# Solar_Charge_Controller.net
KiCad netlist of a schematic drawn in EAGLE
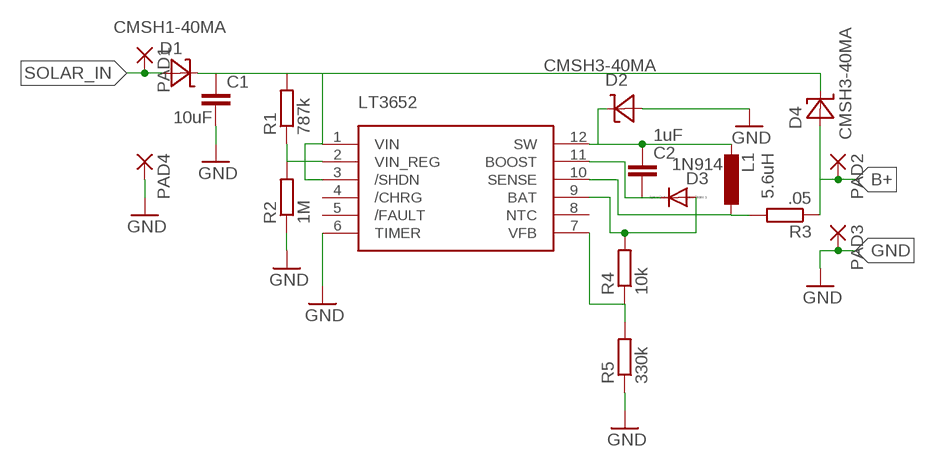
[diagram p0: schematic, sheet 1]

(export (version "E")
  (design (tool "Eeschema 10.0.6"))
  (components
    (comp (ref "C1")
      (value "10uF")
      (footprint "eagle-import:C0805")
      (libsource (lib "eagle-import") (part "C-EUC0805"))
    )
    (comp (ref "C2")
      (value "1uF")
      (footprint "eagle-import:C0603")
      (libsource (lib "eagle-import") (part "C-EUC0603"))
    )
    (comp (ref "D1")
      (value "CMSH1-40MA")
      (footprint "eagle-import:DO-214AC")
      (libsource (lib "eagle-import") (part "CMSH1-40MA"))
    )
    (comp (ref "D2")
      (value "CMSH3-40MA")
      (footprint "eagle-import:DO-214AC")
      (libsource (lib "eagle-import") (part "CMSH3-40MA"))
    )
    (comp (ref "D3")
      (value "1N914")
      (footprint "eagle-import:SOD523")
      (libsource (lib "eagle-import") (part "1N914"))
    )
    (comp (ref "D4")
      (value "CMSH3-40MA")
      (footprint "eagle-import:DO-214AC")
      (libsource (lib "eagle-import") (part "CMSH3-40MA"))
    )
    (comp (ref "L1")
      (value "5.6uH")
      (footprint "eagle-import:1008(2510METRIC)")
      (libsource (lib "eagle-import") (part "L-EU1008"))
    )
    (comp (ref "PAD1")
      (value "SMD5")
      (footprint "eagle-import:SMD2,54-5,08")
      (libsource (lib "eagle-import") (part "SMD5"))
    )
    (comp (ref "PAD2")
      (value "SMD5")
      (footprint "eagle-import:SMD2,54-5,08")
      (libsource (lib "eagle-import") (part "SMD5"))
    )
    (comp (ref "PAD3")
      (value "SMD5")
      (footprint "eagle-import:SMD2,54-5,08")
      (libsource (lib "eagle-import") (part "SMD5"))
    )
    (comp (ref "PAD4")
      (value "SMD5")
      (footprint "eagle-import:SMD2,54-5,08")
      (libsource (lib "eagle-import") (part "SMD5"))
    )
    (comp (ref "R1")
      (value "787k")
      (footprint "eagle-import:R0603")
      (libsource (lib "eagle-import") (part "R-EU_R0603"))
    )
    (comp (ref "R2")
      (value "1M")
      (footprint "eagle-import:R0603")
      (libsource (lib "eagle-import") (part "R-EU_R0603"))
    )
    (comp (ref "R3")
      (value ".05")
      (footprint "eagle-import:R0805")
      (libsource (lib "eagle-import") (part "resistor_R-EU_R0805"))
    )
    (comp (ref "R4")
      (value "10k")
      (footprint "eagle-import:R0603")
      (libsource (lib "eagle-import") (part "R-EU_R0603"))
    )
    (comp (ref "R5")
      (value "330k")
      (footprint "eagle-import:R0603")
      (libsource (lib "eagle-import") (part "R-EU_R0603"))
    )
    (comp (ref "U$1")
      (value "LT3652")
      (footprint "eagle-import:MSOP12")
      (libsource (lib "eagle-import") (part "LT3652"))
    )
  )
  (nets
    (net (code "1") (name "B+") (class "Default")
      (node (ref "D4") (pin "A") (pinfunction "A_A") (pintype "passive"))
      (node (ref "PAD2") (pin "1") (pinfunction "P_1") (pintype "passive"))
      (node (ref "R3") (pin "1") (pinfunction "1_1") (pintype "passive"))
    )
    (net (code "2") (name "GND") (class "Default")
      (node (ref "C1") (pin "2") (pinfunction "2_2") (pintype "passive"))
      (node (ref "D2") (pin "A") (pinfunction "A_A") (pintype "passive"))
      (node (ref "PAD3") (pin "1") (pinfunction "P_1") (pintype "passive"))
      (node (ref "PAD4") (pin "1") (pinfunction "P_1") (pintype "passive"))
      (node (ref "R2") (pin "1") (pinfunction "1_1") (pintype "passive"))
      (node (ref "R5") (pin "1") (pinfunction "1_1") (pintype "passive"))
      (node (ref "U$1") (pin "6") (pinfunction "TIMER_6") (pintype "bidirectional"))
    )
    (net (code "3") (name "Net-(L1-1)") (class "Default")
      (node (ref "L1") (pin "P$2") (pinfunction "1_P$2") (pintype "passive"))
      (node (ref "R3") (pin "2") (pinfunction "2_2") (pintype "passive"))
      (node (ref "U$1") (pin "10") (pinfunction "SENSE_10") (pintype "input"))
    )
    (net (code "4") (name "Net-(L1-2)") (class "Default")
      (node (ref "C2") (pin "1") (pinfunction "1_1") (pintype "passive"))
      (node (ref "D2") (pin "C") (pinfunction "C_C") (pintype "passive"))
      (node (ref "L1") (pin "P$3") (pinfunction "2_P$3") (pintype "passive"))
      (node (ref "U$1") (pin "12") (pinfunction "SW_12") (pintype "output"))
    )
    (net (code "5") (name "Net-(U$1-BAT)") (class "Default")
      (node (ref "D3") (pin "A") (pinfunction "A_A") (pintype "passive"))
      (node (ref "R4") (pin "2") (pinfunction "2_2") (pintype "passive"))
      (node (ref "U$1") (pin "9") (pinfunction "BAT_9") (pintype "bidirectional"))
    )
    (net (code "6") (name "Net-(U$1-BOOST)") (class "Default")
      (node (ref "C2") (pin "2") (pinfunction "2_2") (pintype "passive"))
      (node (ref "D3") (pin "C") (pinfunction "C_C") (pintype "passive"))
      (node (ref "U$1") (pin "11") (pinfunction "BOOST_11") (pintype "output"))
    )
    (net (code "7") (name "Net-(U$1-VFB)") (class "Default")
      (node (ref "R4") (pin "1") (pinfunction "1_1") (pintype "passive"))
      (node (ref "R5") (pin "2") (pinfunction "2_2") (pintype "passive"))
      (node (ref "U$1") (pin "7") (pinfunction "VFB_7") (pintype "input"))
    )
    (net (code "8") (name "Net-(U$1-VIN)") (class "Default")
      (node (ref "C1") (pin "1") (pinfunction "1_1") (pintype "passive"))
      (node (ref "D1") (pin "C") (pinfunction "C_C") (pintype "passive"))
      (node (ref "D4") (pin "C") (pinfunction "C_C") (pintype "passive"))
      (node (ref "R1") (pin "2") (pinfunction "2_2") (pintype "passive"))
      (node (ref "U$1") (pin "1") (pinfunction "VIN_1") (pintype "input"))
      (node (ref "U$1") (pin "3") (pinfunction "/SHDN_3") (pintype "input"))
    )
    (net (code "9") (name "Net-(U$1-VIN_REG)") (class "Default")
      (node (ref "R1") (pin "1") (pinfunction "1_1") (pintype "passive"))
      (node (ref "R2") (pin "2") (pinfunction "2_2") (pintype "passive"))
      (node (ref "U$1") (pin "2") (pinfunction "VIN_REG_2") (pintype "input"))
    )
    (net (code "10") (name "SOLAR_IN") (class "Default")
      (node (ref "D1") (pin "A") (pinfunction "A_A") (pintype "passive"))
      (node (ref "PAD1") (pin "1") (pinfunction "P_1") (pintype "passive"))
    )
    (net (code "11") (name "unconnected-(U$1-NTC-Pad8)") (class "Default")
      (node (ref "U$1") (pin "8") (pinfunction "NTC_8") (pintype "input"))
    )
    (net (code "12") (name "unconnected-(U$1-{slash}CHRG-Pad4)") (class "Default")
      (node (ref "U$1") (pin "4") (pinfunction "/CHRG_4") (pintype "bidirectional"))
    )
    (net (code "13") (name "unconnected-(U$1-{slash}FAULT-Pad5)") (class "Default")
      (node (ref "U$1") (pin "5") (pinfunction "/FAULT_5") (pintype "bidirectional"))
    )
  )
)
